# main_rf.net
KiCad netlist of a schematic drawn in Altium Designer
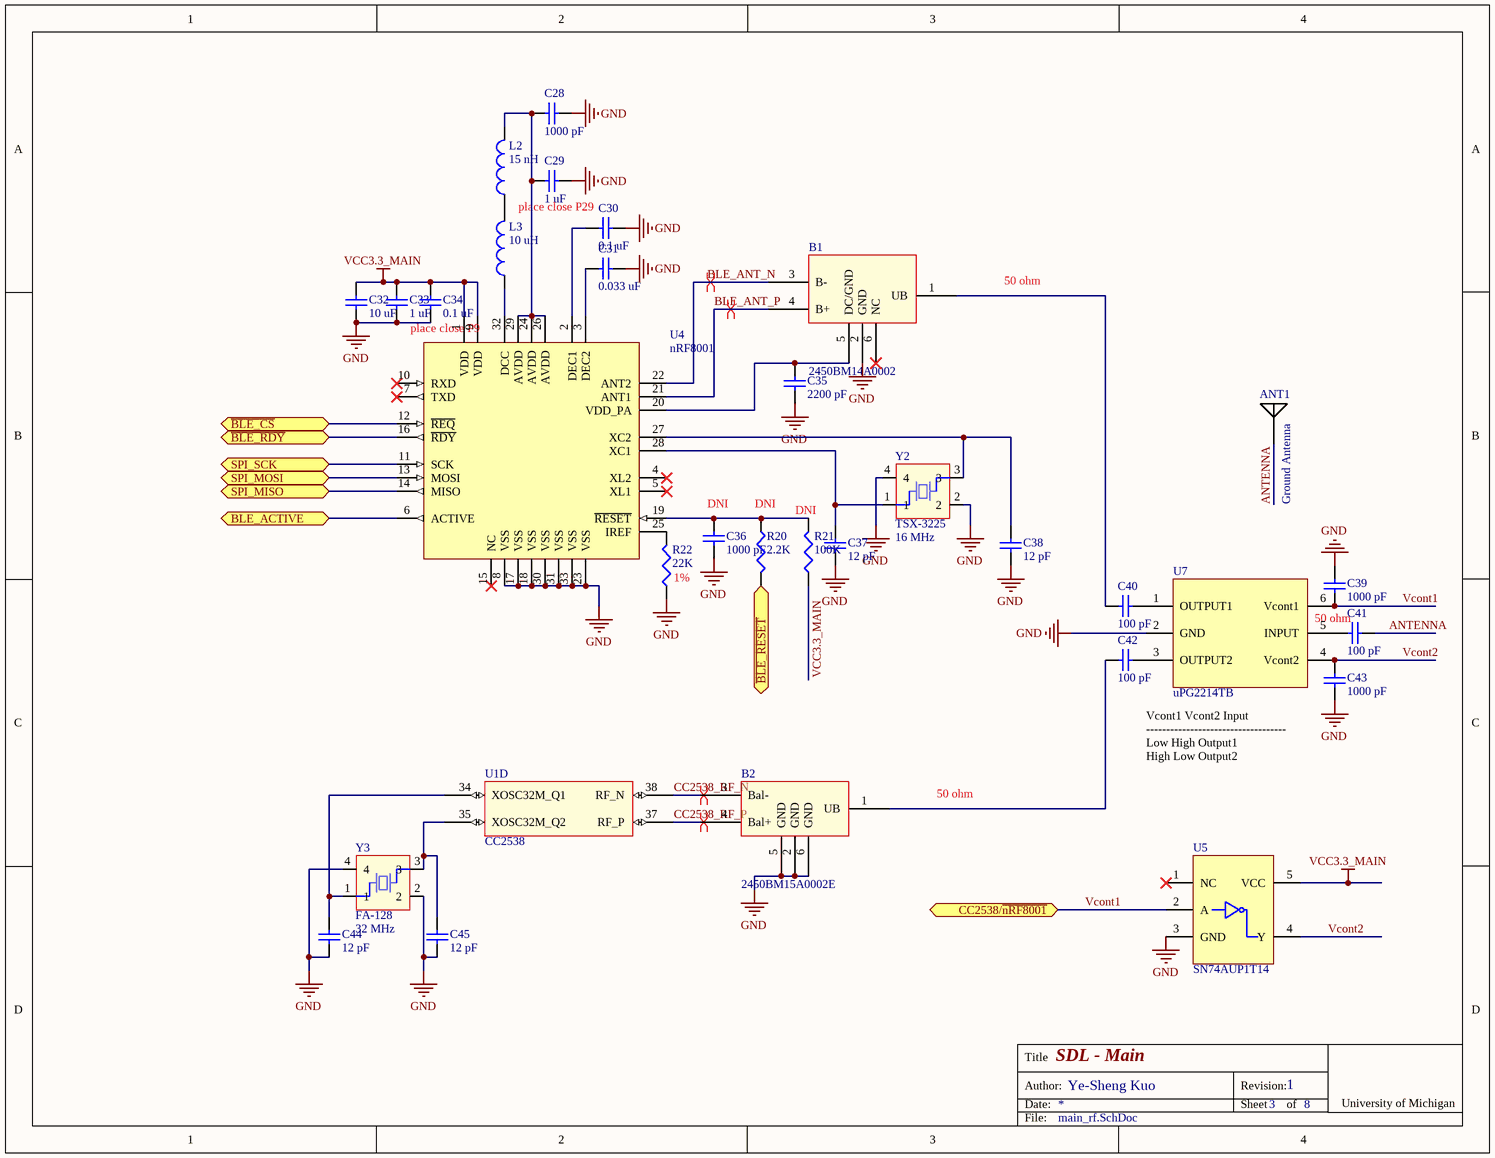
[diagram p0: main_rf.SchDoc]

(export (version "E")
  (design (tool "Eeschema 10.0.6"))
  (components
    (comp (ref "ANT1")
      (value "Ground Antenna")
      (footprint "Chip Antenna")
      (description "2.4GHz Surface Mount Device (SMD) On Ground Antenna, 50 Ohms")
      (libsource (lib "RF") (part "Ground Antenna"))
    )
    (comp (ref "B1")
      (value "2450BM14A0002")
      (footprint "2450BM14A0002")
      (description "2.45 GHz Balun for nRF8001")
      (libsource (lib "RF") (part "2450BM14A0002"))
    )
    (comp (ref "B2")
      (value "2450BM15A0002E")
      (footprint "2450BM15A0002")
      (description "2.45 GHz Balun for TI CC253X")
      (libsource (lib "sdl") (part "2450BM15A0002E"))
    )
    (comp (ref "C28")
      (value "1000 pF")
      (footprint "0402")
      (description "Ceramic capacitor, 1000 pF, 0402 package")
      (fields (field (name "TOLERANCE") "10%") (field (name "Comment") "Ceramic capacitor"))
      (libsource (lib "rlc") (part "C_1000p_0402_ceramic"))
    )
    (comp (ref "C29")
      (value "1 uF")
      (footprint "0603")
      (description "Ceramic capacitor, 1 uF, 0603 package")
      (fields (field (name "TOLERANCE") "10%") (field (name "Comment") "Ceramic capacitor"))
      (libsource (lib "rlc") (part "C_1u_0603_ceramic"))
    )
    (comp (ref "C30")
      (value "0.1 uF")
      (footprint "0402")
      (description "Ceramic capacitor, 0.1u, 0402 package")
      (fields (field (name "TOLERANCE") "10%") (field (name "Comment") "Ceramic capacitor"))
      (libsource (lib "rlc") (part "C_0.1u_0402_ceramic"))
    )
    (comp (ref "C31")
      (value "0.033 uF")
      (footprint "0402")
      (description "Ceramic capacitor, 0.033 uF, 0402 package")
      (fields (field (name "TOLERANCE") "10%") (field (name "Comment") "Ceramic capacitor"))
      (libsource (lib "rlc") (part "C_0.033u_0402_ceramic"))
    )
    (comp (ref "C32")
      (value "10 uF")
      (footprint "0603")
      (description "Ceramic capacitor, 10 uF, 0603 package")
      (fields (field (name "TOLERANCE") "20%") (field (name "Comment") "Ceramic capacitor"))
      (libsource (lib "rlc") (part "C_10u_0603_ceramic"))
    )
    (comp (ref "C33")
      (value "1 uF")
      (footprint "0402")
      (description "Ceramic capacitor, 1 uF, 0402 package")
      (fields (field (name "TOLERANCE") "10%") (field (name "Comment") "Ceramic capacitor"))
      (libsource (lib "rlc") (part "C_1u_0402_ceramic"))
    )
    (comp (ref "C34")
      (value "0.1 uF")
      (footprint "0402")
      (description "Ceramic capacitor, 0.1u, 0402 package")
      (fields (field (name "TOLERANCE") "10%") (field (name "Comment") "Ceramic capacitor"))
      (libsource (lib "rlc") (part "C_0.1u_0402_ceramic"))
    )
    (comp (ref "C35")
      (value "2200 pF")
      (footprint "0402")
      (description "Ceramic capacitor, 2200 pF, 0402 package")
      (fields (field (name "TOLERANCE") "10%") (field (name "Comment") "Ceramic capacitor"))
      (libsource (lib "rlc") (part "C_2200p_0402_ceramic"))
    )
    (comp (ref "C36")
      (value "1000 pF")
      (footprint "0402")
      (description "Ceramic capacitor, 1000 pF, 0402 package")
      (fields (field (name "TOLERANCE") "10%") (field (name "Comment") "Ceramic capacitor"))
      (libsource (lib "rlc") (part "C_1000p_0402_ceramic"))
    )
    (comp (ref "C37")
      (value "12 pF")
      (footprint "0402")
      (description "Ceramic capacitor, 12 pF, 0402 package")
      (fields (field (name "TOLERANCE") "2%") (field (name "Comment") "Ceramic capacitor"))
      (libsource (lib "rlc") (part "C_12p_0402_ceramic"))
    )
    (comp (ref "C38")
      (value "12 pF")
      (footprint "0402")
      (description "Ceramic capacitor, 12 pF, 0402 package")
      (fields (field (name "TOLERANCE") "2%") (field (name "Comment") "Ceramic capacitor"))
      (libsource (lib "rlc") (part "C_12p_0402_ceramic"))
    )
    (comp (ref "C39")
      (value "1000 pF")
      (footprint "0402")
      (description "Ceramic capacitor, 1000 pF, 0402 package")
      (fields (field (name "TOLERANCE") "10%") (field (name "Comment") "Ceramic capacitor"))
      (libsource (lib "rlc") (part "C_1000p_0402_ceramic"))
    )
    (comp (ref "C40")
      (value "100 pF")
      (footprint "0402")
      (description "Ceramic capacitor, 100 pF, 0402 package")
      (fields (field (name "TOLERANCE") "1%") (field (name "Comment") "Ceramic capacitor"))
      (libsource (lib "rlc") (part "C_100p_0402_ceramic"))
    )
    (comp (ref "C41")
      (value "100 pF")
      (footprint "0402")
      (description "Ceramic capacitor, 100 pF, 0402 package")
      (fields (field (name "TOLERANCE") "1%") (field (name "Comment") "Ceramic capacitor"))
      (libsource (lib "rlc") (part "C_100p_0402_ceramic"))
    )
    (comp (ref "C42")
      (value "100 pF")
      (footprint "0402")
      (description "Ceramic capacitor, 100 pF, 0402 package")
      (fields (field (name "TOLERANCE") "1%") (field (name "Comment") "Ceramic capacitor"))
      (libsource (lib "rlc") (part "C_100p_0402_ceramic"))
    )
    (comp (ref "C43")
      (value "1000 pF")
      (footprint "0402")
      (description "Ceramic capacitor, 1000 pF, 0402 package")
      (fields (field (name "TOLERANCE") "10%") (field (name "Comment") "Ceramic capacitor"))
      (libsource (lib "rlc") (part "C_1000p_0402_ceramic"))
    )
    (comp (ref "C44")
      (value "12 pF")
      (footprint "0402")
      (description "Ceramic capacitor, 12 pF, 0402 package")
      (fields (field (name "TOLERANCE") "2%") (field (name "Comment") "Ceramic capacitor"))
      (libsource (lib "rlc") (part "C_12p_0402_ceramic"))
    )
    (comp (ref "C45")
      (value "12 pF")
      (footprint "0402")
      (description "Ceramic capacitor, 12 pF, 0402 package")
      (fields (field (name "TOLERANCE") "2%") (field (name "Comment") "Ceramic capacitor"))
      (libsource (lib "rlc") (part "C_12p_0402_ceramic"))
    )
    (comp (ref "L2")
      (value "15 nH")
      (footprint "0402")
      (description "Chip inductor, 15 nH, 0402 package")
      (fields (field (name "TOLERANCE") "5%") (field (name "Comment") "Chip inductor"))
      (libsource (lib "rlc") (part "L_15n_0402"))
    )
    (comp (ref "L3")
      (value "10 uH")
      (footprint "0603")
      (description "Chip inductor, 10 uH, 0603 package")
      (fields (field (name "TOLERANCE") "20%") (field (name "Comment") "Chip inductor"))
      (libsource (lib "rlc") (part "L_10u_0603"))
    )
    (comp (ref "R20")
      (value "2.2K")
      (footprint "0402")
      (description "Chip resistor, 2.2K, 0402 package")
      (fields (field (name "TOLERANCE") "1%") (field (name "POWER") "1/16 W"))
      (libsource (lib "rlc") (part "R_2.2K_0402"))
    )
    (comp (ref "R21")
      (value "100K")
      (footprint "0402")
      (description "Chip resistor, 100K, 0402 package")
      (fields (field (name "TOLERANCE") "1%") (field (name "POWER") "1/16 W"))
      (libsource (lib "rlc") (part "R_100K_0402"))
    )
    (comp (ref "R22")
      (value "22K")
      (footprint "0402")
      (description "Chip resistor, 22K, 0402 package")
      (fields (field (name "TOLERANCE") "1%") (field (name "POWER") "1/16 W"))
      (libsource (lib "rlc") (part "R_22K_0402"))
    )
    (comp (ref "U1")
      (value "CC2538")
      (footprint "QFN56")
      (description "A Powerful System-On-Chip for 2.4-GHz IEEE 802.15.4, 6LoWPAN  and ZigBee Applications")
      (libsource (lib "sdl") (part "CC2538"))
    )
    (comp (ref "U4")
      (value "nRF8001")
      (footprint "QFN32")
      (description "Single-chip Bluetooth low energy solution")
      (libsource (lib "sdl") (part "nRF8001"))
    )
    (comp (ref "U5")
      (value "SN74AUP1T14")
      (footprint "SC-70-5 (DCK)")
      (description "LOW POWER, 1.8/2.5/3.3-V INPUT, 3.3-V CMOS OUTPUT, SINGLE  SCHMITT-TRIGGER INVERTER GATE")
      (libsource (lib "RF") (part "SN74AUP1T14"))
    )
    (comp (ref "U7")
      (value "uPG2214TB")
      (footprint "minimold-6")
      (description "GaAs Integrated Circuit for L, S-Band SPDT Switch")
      (libsource (lib "RF") (part "uPG2214TB"))
    )
    (comp (ref "Y2")
      (value "TSX-3225")
      (footprint "TSX-3225")
      (description "MHz Range Crystal Unit")
      (fields (field (name "FREQUENCY") "16 MHz"))
      (libsource (lib "crystal_oscillators_rtc") (part "TSX-3225"))
    )
    (comp (ref "Y3")
      (value "FA-128")
      (footprint "FA-128")
      (description "MHz Range Crystal Unit")
      (fields (field (name "FREQUENCY") "32 MHz"))
      (libsource (lib "crystal_oscillators_rtc") (part "FA-128"))
    )
  )
  (nets
    (net (code "1") (name "/ANTENNA") (class "Default")
      (node (ref "ANT1") (pin "1") (pintype "passive"))
      (node (ref "C41") (pin "2") (pintype "passive"))
    )
    (net (code "2") (name "/BLE_ACTIVE") (class "Default")
      (node (ref "U4") (pin "6") (pinfunction "ACTIVE_6") (pintype "output"))
    )
    (net (code "3") (name "/BLE_ANT_N") (class "Default")
      (node (ref "B1") (pin "3") (pinfunction "B-_3") (pintype "passive"))
      (node (ref "U4") (pin "22") (pinfunction "ANT2_22") (pintype "passive"))
    )
    (net (code "4") (name "/BLE_ANT_P") (class "Default")
      (node (ref "B1") (pin "4") (pinfunction "B+_4") (pintype "passive"))
      (node (ref "U4") (pin "21") (pinfunction "ANT1_21") (pintype "passive"))
    )
    (net (code "5") (name "/CC2538_RF_N") (class "Default")
      (node (ref "B2") (pin "3") (pinfunction "Bal-_3") (pintype "passive"))
      (node (ref "U1") (pin "38") (pinfunction "RF_N_38") (pintype "bidirectional"))
    )
    (net (code "6") (name "/CC2538_RF_P") (class "Default")
      (node (ref "B2") (pin "4") (pinfunction "Bal+_4") (pintype "passive"))
      (node (ref "U1") (pin "37") (pinfunction "RF_P_37") (pintype "bidirectional"))
    )
    (net (code "7") (name "/SPI_MISO") (class "Default")
      (node (ref "U4") (pin "14") (pinfunction "MISO_14") (pintype "output"))
    )
    (net (code "8") (name "/SPI_MOSI") (class "Default")
      (node (ref "U4") (pin "13") (pinfunction "MOSI_13") (pintype "input"))
    )
    (net (code "9") (name "/SPI_SCK") (class "Default")
      (node (ref "U4") (pin "11") (pinfunction "SCK_11") (pintype "input"))
    )
    (net (code "10") (name "/Vcont1") (class "Default")
      (node (ref "C39") (pin "2") (pintype "passive"))
      (node (ref "U5") (pin "2") (pinfunction "A_2") (pintype "power_in"))
      (node (ref "U7") (pin "6") (pinfunction "Vcont1_6") (pintype "power_in"))
    )
    (net (code "11") (name "/Vcont2") (class "Default")
      (node (ref "C43") (pin "1") (pintype "passive"))
      (node (ref "U5") (pin "4") (pinfunction "Y_4") (pintype "power_in"))
      (node (ref "U7") (pin "4") (pinfunction "Vcont2_4") (pintype "power_in"))
    )
    (net (code "12") (name "/~{BLE_CS}") (class "Default")
      (node (ref "U4") (pin "12") (pinfunction "~{REQ}_12") (pintype "input"))
    )
    (net (code "13") (name "/~{BLE_RDY}") (class "Default")
      (node (ref "U4") (pin "16") (pinfunction "~{RDY}_16") (pintype "output"))
    )
    (net (code "14") (name "/~{BLE_RESET}") (class "Default")
      (node (ref "R20") (pin "1") (pintype "passive"))
    )
    (net (code "15") (name "GND") (class "Default")
      (node (ref "B1") (pin "2") (pinfunction "GND_2") (pintype "passive"))
      (node (ref "B2") (pin "2") (pinfunction "GND_2") (pintype "passive"))
      (node (ref "B2") (pin "5") (pinfunction "GND_5") (pintype "passive"))
      (node (ref "B2") (pin "6") (pinfunction "GND_6") (pintype "passive"))
      (node (ref "C28") (pin "2") (pintype "passive"))
      (node (ref "C29") (pin "2") (pintype "passive"))
      (node (ref "C30") (pin "2") (pintype "passive"))
      (node (ref "C31") (pin "2") (pintype "passive"))
      (node (ref "C32") (pin "2") (pintype "passive"))
      (node (ref "C33") (pin "2") (pintype "passive"))
      (node (ref "C34") (pin "2") (pintype "passive"))
      (node (ref "C35") (pin "2") (pintype "passive"))
      (node (ref "C36") (pin "2") (pintype "passive"))
      (node (ref "C37") (pin "2") (pintype "passive"))
      (node (ref "C38") (pin "2") (pintype "passive"))
      (node (ref "C39") (pin "1") (pintype "passive"))
      (node (ref "C43") (pin "2") (pintype "passive"))
      (node (ref "C44") (pin "1") (pintype "passive"))
      (node (ref "C45") (pin "1") (pintype "passive"))
      (node (ref "R22") (pin "2") (pintype "passive"))
      (node (ref "U4") (pin "17") (pinfunction "VSS_17") (pintype "passive"))
      (node (ref "U4") (pin "18") (pinfunction "VSS_18") (pintype "passive"))
      (node (ref "U4") (pin "23") (pinfunction "VSS_23") (pintype "power_in"))
      (node (ref "U4") (pin "30") (pinfunction "VSS_30") (pintype "power_in"))
      (node (ref "U4") (pin "31") (pinfunction "VSS_31") (pintype "power_in"))
      (node (ref "U4") (pin "33") (pinfunction "VSS_33") (pintype "power_in"))
      (node (ref "U4") (pin "8") (pinfunction "VSS_8") (pintype "power_in"))
      (node (ref "U5") (pin "3") (pinfunction "GND_3") (pintype "power_in"))
      (node (ref "U7") (pin "2") (pinfunction "GND_2") (pintype "power_in"))
      (node (ref "Y2") (pin "2") (pinfunction "2_2") (pintype "passive"))
      (node (ref "Y2") (pin "4") (pinfunction "4_4") (pintype "passive"))
      (node (ref "Y3") (pin "2") (pinfunction "2_2") (pintype "passive"))
      (node (ref "Y3") (pin "4") (pinfunction "4_4") (pintype "passive"))
    )
    (net (code "16") (name "Net-(B1-DC{slash}GND)") (class "Default")
      (node (ref "B1") (pin "5") (pinfunction "DC/GND_5") (pintype "passive"))
      (node (ref "C35") (pin "1") (pintype "passive"))
      (node (ref "U4") (pin "20") (pinfunction "VDD_PA_20") (pintype "power_in"))
    )
    (net (code "17") (name "Net-(B1-UB)") (class "Default")
      (node (ref "B1") (pin "1") (pinfunction "UB_1") (pintype "passive"))
      (node (ref "C40") (pin "1") (pintype "passive"))
    )
    (net (code "18") (name "Net-(B2-UB)") (class "Default")
      (node (ref "B2") (pin "1") (pinfunction "UB_1") (pintype "passive"))
      (node (ref "C42") (pin "1") (pintype "passive"))
    )
    (net (code "19") (name "Net-(C28-Pad1)") (class "Default")
      (node (ref "C28") (pin "1") (pintype "passive"))
      (node (ref "C29") (pin "1") (pintype "passive"))
      (node (ref "L2") (pin "1") (pintype "passive"))
      (node (ref "U4") (pin "24") (pinfunction "AVDD_24") (pintype "power_in"))
      (node (ref "U4") (pin "26") (pinfunction "AVDD_26") (pintype "passive"))
      (node (ref "U4") (pin "29") (pinfunction "AVDD_29") (pintype "power_in"))
    )
    (net (code "20") (name "Net-(L2-Pad2)") (class "Default")
      (node (ref "L2") (pin "2") (pintype "passive"))
      (node (ref "L3") (pin "1") (pintype "passive"))
    )
    (net (code "21") (name "Net-(U1D-XOSC32M_Q1)") (class "Default")
      (node (ref "C44") (pin "2") (pintype "passive"))
      (node (ref "U1") (pin "34") (pinfunction "XOSC32M_Q1_34") (pintype "bidirectional"))
      (node (ref "Y3") (pin "1") (pinfunction "1_1") (pintype "passive"))
    )
    (net (code "22") (name "Net-(U1D-XOSC32M_Q2)") (class "Default")
      (node (ref "C45") (pin "2") (pintype "passive"))
      (node (ref "U1") (pin "35") (pinfunction "XOSC32M_Q2_35") (pintype "bidirectional"))
      (node (ref "Y3") (pin "3") (pinfunction "3_3") (pintype "passive"))
    )
    (net (code "23") (name "Net-(U4-DCC)") (class "Default")
      (node (ref "L3") (pin "2") (pintype "passive"))
      (node (ref "U4") (pin "32") (pinfunction "DCC_32") (pintype "power_in"))
    )
    (net (code "24") (name "Net-(U4-DEC1)") (class "Default")
      (node (ref "C30") (pin "1") (pintype "passive"))
      (node (ref "U4") (pin "2") (pinfunction "DEC1_2") (pintype "power_in"))
    )
    (net (code "25") (name "Net-(U4-DEC2)") (class "Default")
      (node (ref "C31") (pin "1") (pintype "passive"))
      (node (ref "U4") (pin "3") (pinfunction "DEC2_3") (pintype "power_in"))
    )
    (net (code "26") (name "Net-(U4-IREF)") (class "Default")
      (node (ref "R22") (pin "1") (pintype "passive"))
      (node (ref "U4") (pin "25") (pinfunction "IREF_25") (pintype "passive"))
    )
    (net (code "27") (name "Net-(U4-XC1)") (class "Default")
      (node (ref "C37") (pin "1") (pintype "passive"))
      (node (ref "U4") (pin "28") (pinfunction "XC1_28") (pintype "passive"))
      (node (ref "Y2") (pin "1") (pinfunction "1_1") (pintype "passive"))
    )
    (net (code "28") (name "Net-(U4-XC2)") (class "Default")
      (node (ref "C38") (pin "1") (pintype "passive"))
      (node (ref "U4") (pin "27") (pinfunction "XC2_27") (pintype "passive"))
      (node (ref "Y2") (pin "3") (pinfunction "3_3") (pintype "passive"))
    )
    (net (code "29") (name "Net-(U4-~{RESET})") (class "Default")
      (node (ref "C36") (pin "1") (pintype "passive"))
      (node (ref "R20") (pin "2") (pintype "passive"))
      (node (ref "R21") (pin "1") (pintype "passive"))
      (node (ref "U4") (pin "19") (pinfunction "~{RESET}_19") (pintype "input"))
    )
    (net (code "30") (name "Net-(U7-INPUT)") (class "Default")
      (node (ref "C41") (pin "1") (pintype "passive"))
      (node (ref "U7") (pin "5") (pinfunction "INPUT_5") (pintype "power_in"))
    )
    (net (code "31") (name "Net-(U7-OUTPUT1)") (class "Default")
      (node (ref "C40") (pin "2") (pintype "passive"))
      (node (ref "U7") (pin "1") (pinfunction "OUTPUT1_1") (pintype "power_in"))
    )
    (net (code "32") (name "Net-(U7-OUTPUT2)") (class "Default")
      (node (ref "C42") (pin "2") (pintype "passive"))
      (node (ref "U7") (pin "3") (pinfunction "OUTPUT2_3") (pintype "power_in"))
    )
    (net (code "33") (name "VCC3.3_MAIN") (class "Default")
      (node (ref "C32") (pin "1") (pintype "passive"))
      (node (ref "C33") (pin "1") (pintype "passive"))
      (node (ref "C34") (pin "1") (pintype "passive"))
      (node (ref "R21") (pin "2") (pintype "passive"))
      (node (ref "U4") (pin "1") (pinfunction "VDD_1") (pintype "power_in"))
      (node (ref "U4") (pin "9") (pinfunction "VDD_9") (pintype "power_in"))
      (node (ref "U5") (pin "5") (pinfunction "VCC_5") (pintype "power_in"))
    )
    (net (code "34") (name "unconnected-(B1-NC-Pad6)") (class "Default")
      (node (ref "B1") (pin "6") (pinfunction "NC_6") (pintype "passive+no_connect"))
    )
    (net (code "35") (name "unconnected-(U4-NC-Pad15)") (class "Default")
      (node (ref "U4") (pin "15") (pinfunction "NC_15") (pintype "passive+no_connect"))
    )
    (net (code "36") (name "unconnected-(U4-RXD-Pad10)") (class "Default")
      (node (ref "U4") (pin "10") (pinfunction "RXD_10") (pintype "input+no_connect"))
    )
    (net (code "37") (name "unconnected-(U4-TXD-Pad7)") (class "Default")
      (node (ref "U4") (pin "7") (pinfunction "TXD_7") (pintype "output+no_connect"))
    )
    (net (code "38") (name "unconnected-(U4-XL1-Pad5)") (class "Default")
      (node (ref "U4") (pin "5") (pinfunction "XL1_5") (pintype "passive+no_connect"))
    )
    (net (code "39") (name "unconnected-(U4-XL2-Pad4)") (class "Default")
      (node (ref "U4") (pin "4") (pinfunction "XL2_4") (pintype "passive+no_connect"))
    )
    (net (code "40") (name "unconnected-(U5-NC-Pad1)") (class "Default")
      (node (ref "U5") (pin "1") (pinfunction "NC_1") (pintype "power_in+no_connect"))
    )
  )
)
